# umami-blade.net
KiCad netlist of a schematic drawn in EAGLE
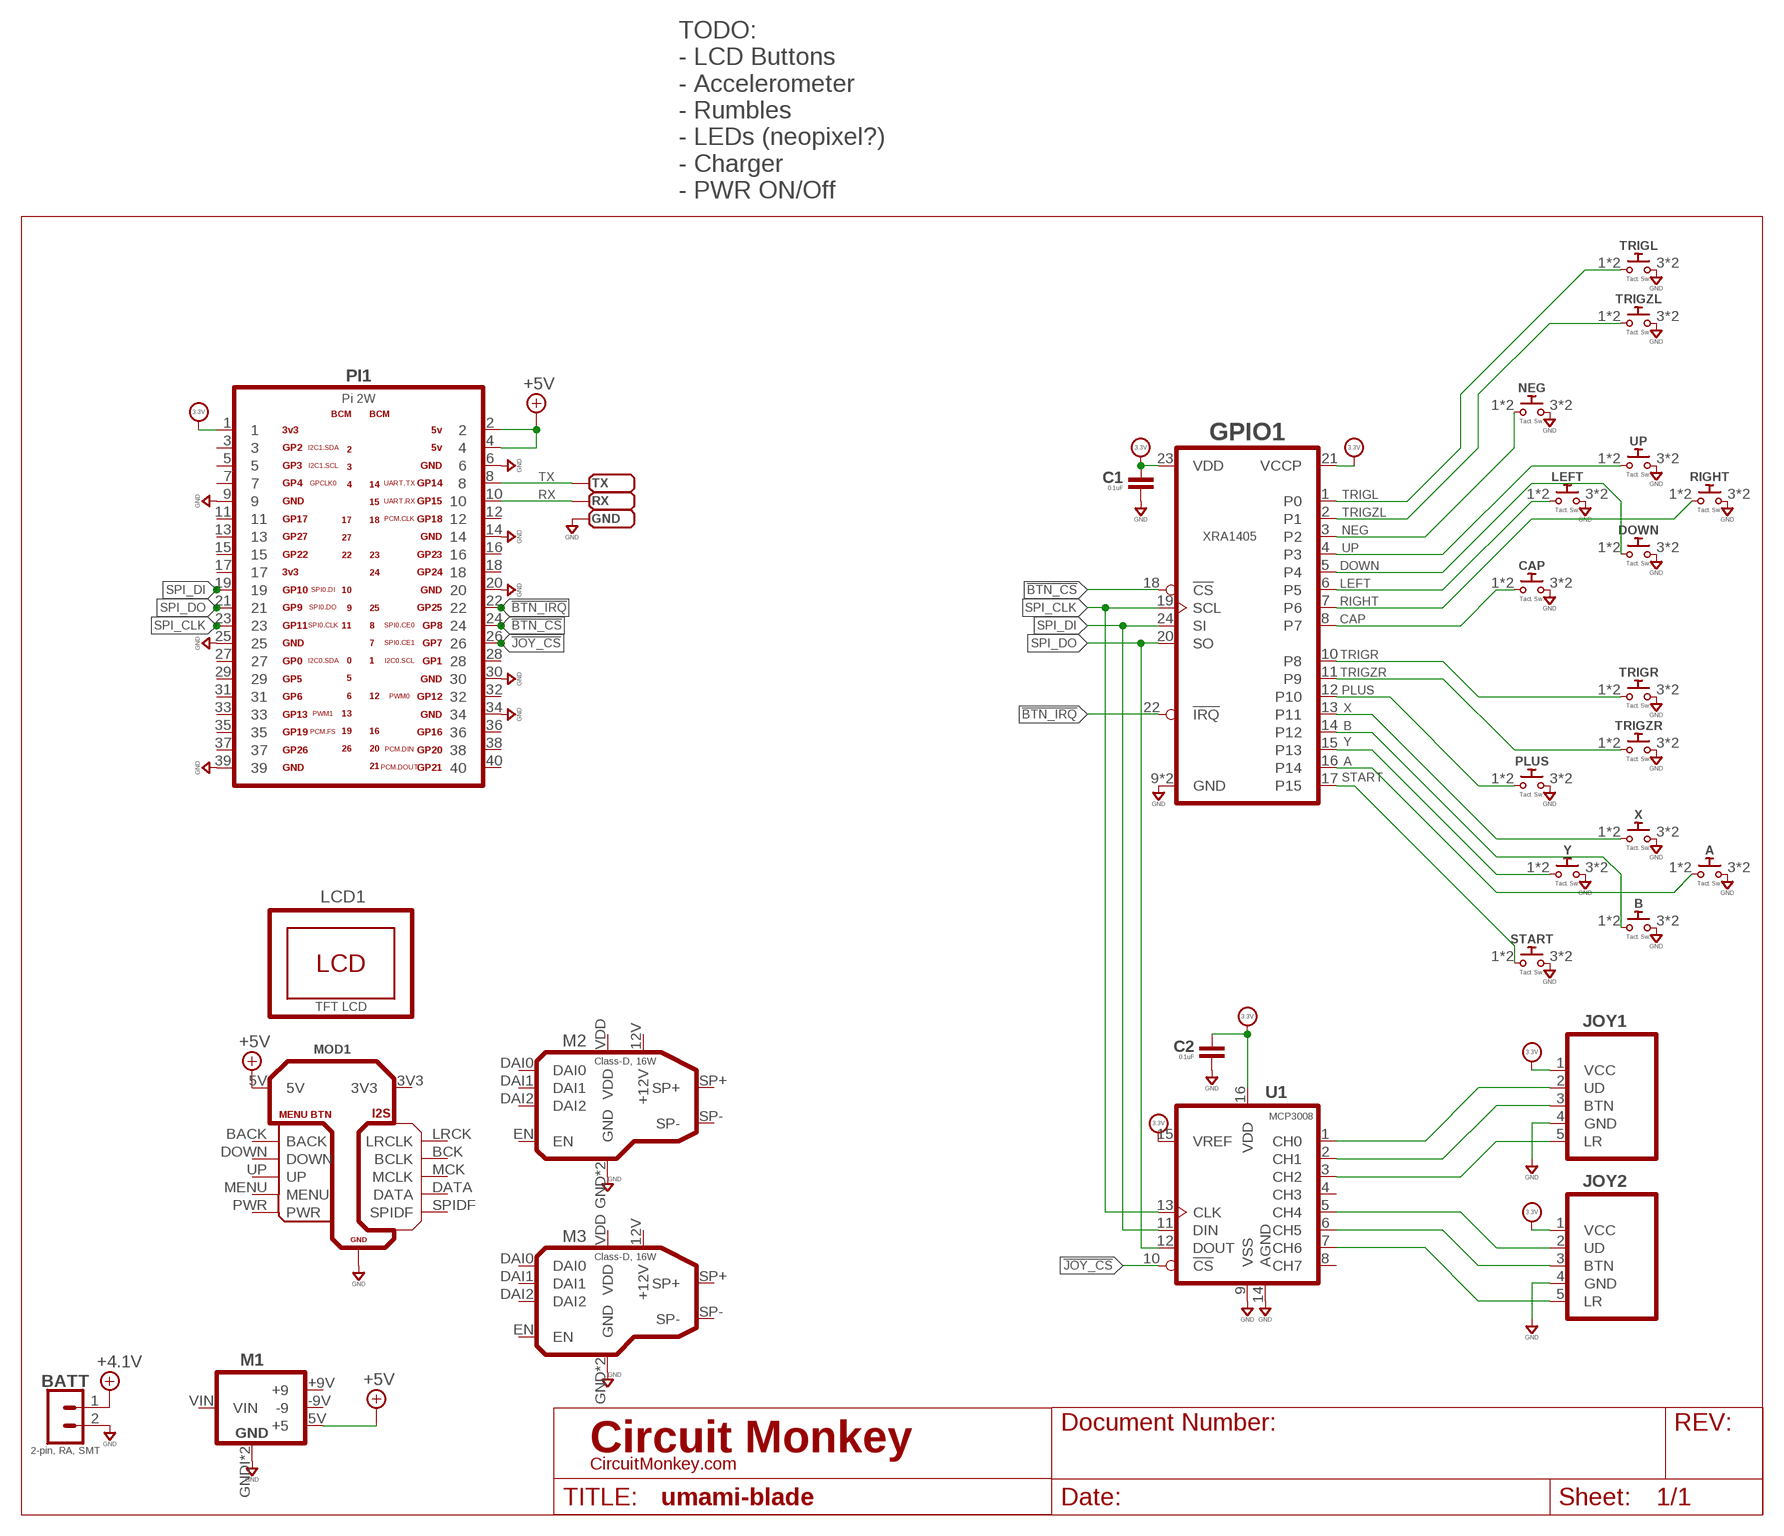
[diagram p0: schematic, sheet 1]

(export (version "E")
  (design (tool "Eeschema 10.0.6"))
  (components
    (comp (ref "A")
      (value "Tact. Sw.")
      (footprint "eagle-import:B3FS")
      (fields (field (name "MFR") "Omron") (field (name "MPN") "B3FS-10*"))
      (libsource (lib "eagle-import") (part "PUSHBTN-MOMB3FS"))
    )
    (comp (ref "B")
      (value "Tact. Sw.")
      (footprint "eagle-import:B3FS")
      (fields (field (name "MFR") "Omron") (field (name "MPN") "B3FS-10*"))
      (libsource (lib "eagle-import") (part "PUSHBTN-MOMB3FS"))
    )
    (comp (ref "BATT")
      (value "2-pin, RA, SMT")
      (footprint "eagle-import:S2B-PH-SM4-")
      (fields (field (name "MFR") "JST") (field (name "MPN") "S2B-PH-SM4"))
      (libsource (lib "eagle-import") (part "02PRA-SMT"))
    )
    (comp (ref "C1")
      (value "0.1uF")
      (footprint "eagle-import:0603-CAP")
      (libsource (lib "eagle-import") (part "CAPACITOR0603"))
    )
    (comp (ref "C2")
      (value "0.1uF")
      (footprint "eagle-import:0603-CAP")
      (libsource (lib "eagle-import") (part "CAPACITOR0603"))
    )
    (comp (ref "CAP")
      (value "Tact. Sw.")
      (footprint "eagle-import:B3FS")
      (fields (field (name "MFR") "Omron") (field (name "MPN") "B3FS-10*"))
      (libsource (lib "eagle-import") (part "PUSHBTN-MOMB3FS"))
    )
    (comp (ref "DOWN")
      (value "Tact. Sw.")
      (footprint "eagle-import:B3FS")
      (fields (field (name "MFR") "Omron") (field (name "MPN") "B3FS-10*"))
      (libsource (lib "eagle-import") (part "PUSHBTN-MOMB3FS"))
    )
    (comp (ref "GND")
      (value "PADSMD-050X050")
      (footprint "eagle-import:SMD-050X050")
      (libsource (lib "eagle-import") (part "PADSMD-050X050"))
    )
    (comp (ref "GPIO1")
      (value "XRA1405")
      (footprint "eagle-import:QFN-24")
      (fields (field (name "MFR") "Exar") (field (name "MPN") "XRA1405IL24"))
      (libsource (lib "eagle-import") (part "XRA1405IL24"))
    )
    (comp (ref "JOY1")
      (value "THUMBSTICKNINTENDO-SWITCH")
      (footprint "eagle-import:NINTENDO-JOYCON")
      (libsource (lib "eagle-import") (part "THUMBSTICKNINTENDO-SWITCH"))
    )
    (comp (ref "JOY2")
      (value "THUMBSTICKNINTENDO-SWITCH")
      (footprint "eagle-import:NINTENDO-JOYCON")
      (libsource (lib "eagle-import") (part "THUMBSTICKNINTENDO-SWITCH"))
    )
    (comp (ref "LCD1")
      (value "TFT LCD")
      (footprint "eagle-import:PIMORONI_PIM372")
      (fields (field (name "MPN") "PIM372"))
      (libsource (lib "eagle-import") (part "LCD_MOCKUPPIM372"))
    )
    (comp (ref "LEFT")
      (value "Tact. Sw.")
      (footprint "eagle-import:B3FS")
      (fields (field (name "MFR") "Omron") (field (name "MPN") "B3FS-10*"))
      (libsource (lib "eagle-import") (part "PUSHBTN-MOMB3FS"))
    )
    (comp (ref "M1")
      (value "0128REV-A")
      (footprint "eagle-import:0128A")
      (libsource (lib "eagle-import") (part "0128REV-A"))
    )
    (comp (ref "M2")
      (value "Class-D, 16W")
      (footprint "eagle-import:0123A")
      (fields (field (name "MFR") "Circuit Monkey") (field (name "MPN") "0123A"))
      (libsource (lib "eagle-import") (part "0123REV-A"))
    )
    (comp (ref "M3")
      (value "Class-D, 16W")
      (footprint "eagle-import:0123A")
      (fields (field (name "MFR") "Circuit Monkey") (field (name "MPN") "0123A"))
      (libsource (lib "eagle-import") (part "0123REV-A"))
    )
    (comp (ref "MOD1")
      (value "LCD_CONTROLLERPIMORONI-8IN")
      (footprint "eagle-import:PIMORONI-LCD-CONTROLLER")
      (libsource (lib "eagle-import") (part "LCD_CONTROLLERPIMORONI-8IN"))
    )
    (comp (ref "NEG")
      (value "Tact. Sw.")
      (footprint "eagle-import:B3FS")
      (fields (field (name "MFR") "Omron") (field (name "MPN") "B3FS-10*"))
      (libsource (lib "eagle-import") (part "PUSHBTN-MOMB3FS"))
    )
    (comp (ref "PI1")
      (value "Pi 2W")
      (footprint "eagle-import:PI-ZERO-2W")
      (libsource (lib "eagle-import") (part "RASPBERRY_PI-ZERO-2W"))
    )
    (comp (ref "PLUS")
      (value "Tact. Sw.")
      (footprint "eagle-import:B3FS")
      (fields (field (name "MFR") "Omron") (field (name "MPN") "B3FS-10*"))
      (libsource (lib "eagle-import") (part "PUSHBTN-MOMB3FS"))
    )
    (comp (ref "RIGHT")
      (value "Tact. Sw.")
      (footprint "eagle-import:B3FS")
      (fields (field (name "MFR") "Omron") (field (name "MPN") "B3FS-10*"))
      (libsource (lib "eagle-import") (part "PUSHBTN-MOMB3FS"))
    )
    (comp (ref "RX")
      (value "PADSMD-050X050")
      (footprint "eagle-import:SMD-050X050")
      (libsource (lib "eagle-import") (part "PADSMD-050X050"))
    )
    (comp (ref "START")
      (value "Tact. Sw.")
      (footprint "eagle-import:B3FS")
      (fields (field (name "MFR") "Omron") (field (name "MPN") "B3FS-10*"))
      (libsource (lib "eagle-import") (part "PUSHBTN-MOMB3FS"))
    )
    (comp (ref "TRIGL")
      (value "Tact. Sw.")
      (footprint "eagle-import:B3FS")
      (fields (field (name "MFR") "Omron") (field (name "MPN") "B3FS-10*"))
      (libsource (lib "eagle-import") (part "PUSHBTN-MOMB3FS"))
    )
    (comp (ref "TRIGR")
      (value "Tact. Sw.")
      (footprint "eagle-import:B3FS")
      (fields (field (name "MFR") "Omron") (field (name "MPN") "B3FS-10*"))
      (libsource (lib "eagle-import") (part "PUSHBTN-MOMB3FS"))
    )
    (comp (ref "TRIGZL")
      (value "Tact. Sw.")
      (footprint "eagle-import:B3FS")
      (fields (field (name "MFR") "Omron") (field (name "MPN") "B3FS-10*"))
      (libsource (lib "eagle-import") (part "PUSHBTN-MOMB3FS"))
    )
    (comp (ref "TRIGZR")
      (value "Tact. Sw.")
      (footprint "eagle-import:B3FS")
      (fields (field (name "MFR") "Omron") (field (name "MPN") "B3FS-10*"))
      (libsource (lib "eagle-import") (part "PUSHBTN-MOMB3FS"))
    )
    (comp (ref "TX")
      (value "PADSMD-050X050")
      (footprint "eagle-import:SMD-050X050")
      (libsource (lib "eagle-import") (part "PADSMD-050X050"))
    )
    (comp (ref "U1")
      (value "MCP3008")
      (footprint "eagle-import:SO16")
      (fields (field (name "MFR") "Microchip") (field (name "MPN") "MCP3008-I/SL"))
      (libsource (lib "eagle-import") (part "MCP3008SO16"))
    )
    (comp (ref "UP")
      (value "Tact. Sw.")
      (footprint "eagle-import:B3FS")
      (fields (field (name "MFR") "Omron") (field (name "MPN") "B3FS-10*"))
      (libsource (lib "eagle-import") (part "PUSHBTN-MOMB3FS"))
    )
    (comp (ref "X")
      (value "Tact. Sw.")
      (footprint "eagle-import:B3FS")
      (fields (field (name "MFR") "Omron") (field (name "MPN") "B3FS-10*"))
      (libsource (lib "eagle-import") (part "PUSHBTN-MOMB3FS"))
    )
    (comp (ref "Y")
      (value "Tact. Sw.")
      (footprint "eagle-import:B3FS")
      (fields (field (name "MFR") "Omron") (field (name "MPN") "B3FS-10*"))
      (libsource (lib "eagle-import") (part "PUSHBTN-MOMB3FS"))
    )
  )
  (nets
    (net (code "1") (name "+4.1V") (class "Default")
      (node (ref "BATT") (pin "1") (pinfunction "1_1") (pintype "passive"))
    )
    (net (code "2") (name "+5V") (class "Default")
      (node (ref "M1") (pin "5V") (pinfunction "+5_5V") (pintype "bidirectional"))
      (node (ref "MOD1") (pin "5V") (pinfunction "5V_5V") (pintype "power_in"))
      (node (ref "PI1") (pin "2") (pinfunction "2_2") (pintype "bidirectional"))
      (node (ref "PI1") (pin "4") (pinfunction "4_4") (pintype "bidirectional"))
    )
    (net (code "3") (name "/A") (class "Default")
      (node (ref "A") (pin "1") (pinfunction "1_1") (pintype "passive"))
      (node (ref "A") (pin "2") (pinfunction "1_2") (pintype "passive"))
      (node (ref "GPIO1") (pin "16") (pinfunction "P14_16") (pintype "bidirectional"))
    )
    (net (code "4") (name "/B") (class "Default")
      (node (ref "B") (pin "1") (pinfunction "1_1") (pintype "passive"))
      (node (ref "B") (pin "2") (pinfunction "1_2") (pintype "passive"))
      (node (ref "GPIO1") (pin "14") (pinfunction "P12_14") (pintype "bidirectional"))
    )
    (net (code "5") (name "/CAP") (class "Default")
      (node (ref "CAP") (pin "1") (pinfunction "1_1") (pintype "passive"))
      (node (ref "CAP") (pin "2") (pinfunction "1_2") (pintype "passive"))
      (node (ref "GPIO1") (pin "8") (pinfunction "P7_8") (pintype "bidirectional"))
    )
    (net (code "6") (name "/DOWN") (class "Default")
      (node (ref "DOWN") (pin "1") (pinfunction "1_1") (pintype "passive"))
      (node (ref "DOWN") (pin "2") (pinfunction "1_2") (pintype "passive"))
      (node (ref "GPIO1") (pin "5") (pinfunction "P4_5") (pintype "bidirectional"))
    )
    (net (code "7") (name "/LEFT") (class "Default")
      (node (ref "GPIO1") (pin "6") (pinfunction "P5_6") (pintype "bidirectional"))
      (node (ref "LEFT") (pin "1") (pinfunction "1_1") (pintype "passive"))
      (node (ref "LEFT") (pin "2") (pinfunction "1_2") (pintype "passive"))
    )
    (net (code "8") (name "/NEG") (class "Default")
      (node (ref "GPIO1") (pin "3") (pinfunction "P2_3") (pintype "bidirectional"))
      (node (ref "NEG") (pin "1") (pinfunction "1_1") (pintype "passive"))
      (node (ref "NEG") (pin "2") (pinfunction "1_2") (pintype "passive"))
    )
    (net (code "9") (name "/PLUS") (class "Default")
      (node (ref "GPIO1") (pin "12") (pinfunction "P10_12") (pintype "bidirectional"))
      (node (ref "PLUS") (pin "1") (pinfunction "1_1") (pintype "passive"))
      (node (ref "PLUS") (pin "2") (pinfunction "1_2") (pintype "passive"))
    )
    (net (code "10") (name "/RIGHT") (class "Default")
      (node (ref "GPIO1") (pin "7") (pinfunction "P6_7") (pintype "bidirectional"))
      (node (ref "RIGHT") (pin "1") (pinfunction "1_1") (pintype "passive"))
      (node (ref "RIGHT") (pin "2") (pinfunction "1_2") (pintype "passive"))
    )
    (net (code "11") (name "/RX") (class "Default")
      (node (ref "PI1") (pin "10") (pinfunction "10_10") (pintype "bidirectional"))
      (node (ref "RX") (pin "1") (pinfunction "PAD_1") (pintype "bidirectional"))
    )
    (net (code "12") (name "/START") (class "Default")
      (node (ref "GPIO1") (pin "17") (pinfunction "P15_17") (pintype "bidirectional"))
      (node (ref "START") (pin "1") (pinfunction "1_1") (pintype "passive"))
      (node (ref "START") (pin "2") (pinfunction "1_2") (pintype "passive"))
    )
    (net (code "13") (name "/TRIGL") (class "Default")
      (node (ref "GPIO1") (pin "1") (pinfunction "P0_1") (pintype "bidirectional"))
      (node (ref "TRIGL") (pin "1") (pinfunction "1_1") (pintype "passive"))
      (node (ref "TRIGL") (pin "2") (pinfunction "1_2") (pintype "passive"))
    )
    (net (code "14") (name "/TRIGR") (class "Default")
      (node (ref "GPIO1") (pin "10") (pinfunction "P8_10") (pintype "bidirectional"))
      (node (ref "TRIGR") (pin "1") (pinfunction "1_1") (pintype "passive"))
      (node (ref "TRIGR") (pin "2") (pinfunction "1_2") (pintype "passive"))
    )
    (net (code "15") (name "/TRIGZL") (class "Default")
      (node (ref "GPIO1") (pin "2") (pinfunction "P1_2") (pintype "bidirectional"))
      (node (ref "TRIGZL") (pin "1") (pinfunction "1_1") (pintype "passive"))
      (node (ref "TRIGZL") (pin "2") (pinfunction "1_2") (pintype "passive"))
    )
    (net (code "16") (name "/TRIGZR") (class "Default")
      (node (ref "GPIO1") (pin "11") (pinfunction "P9_11") (pintype "bidirectional"))
      (node (ref "TRIGZR") (pin "1") (pinfunction "1_1") (pintype "passive"))
      (node (ref "TRIGZR") (pin "2") (pinfunction "1_2") (pintype "passive"))
    )
    (net (code "17") (name "/TX") (class "Default")
      (node (ref "PI1") (pin "8") (pinfunction "8_8") (pintype "bidirectional"))
      (node (ref "TX") (pin "1") (pinfunction "PAD_1") (pintype "bidirectional"))
    )
    (net (code "18") (name "/UP") (class "Default")
      (node (ref "GPIO1") (pin "4") (pinfunction "P3_4") (pintype "bidirectional"))
      (node (ref "UP") (pin "1") (pinfunction "1_1") (pintype "passive"))
      (node (ref "UP") (pin "2") (pinfunction "1_2") (pintype "passive"))
    )
    (net (code "19") (name "/X") (class "Default")
      (node (ref "GPIO1") (pin "13") (pinfunction "P11_13") (pintype "bidirectional"))
      (node (ref "X") (pin "1") (pinfunction "1_1") (pintype "passive"))
      (node (ref "X") (pin "2") (pinfunction "1_2") (pintype "passive"))
    )
    (net (code "20") (name "/Y") (class "Default")
      (node (ref "GPIO1") (pin "15") (pinfunction "P13_15") (pintype "bidirectional"))
      (node (ref "Y") (pin "1") (pinfunction "1_1") (pintype "passive"))
      (node (ref "Y") (pin "2") (pinfunction "1_2") (pintype "passive"))
    )
    (net (code "21") (name "/~{BTN_CS}") (class "Default")
      (node (ref "GPIO1") (pin "18") (pinfunction "~{CS}_18") (pintype "input"))
      (node (ref "PI1") (pin "24") (pinfunction "24_24") (pintype "bidirectional"))
    )
    (net (code "22") (name "/~{BTN_IRQ}") (class "Default")
      (node (ref "GPIO1") (pin "22") (pinfunction "~{IRQ}_22") (pintype "output"))
      (node (ref "PI1") (pin "22") (pinfunction "22_22") (pintype "bidirectional"))
    )
    (net (code "23") (name "/~{JOY_CS}") (class "Default")
      (node (ref "PI1") (pin "26") (pinfunction "26_26") (pintype "bidirectional"))
      (node (ref "U1") (pin "10") (pinfunction "~{CS}_10") (pintype "input"))
    )
    (net (code "24") (name "3.3V") (class "Default")
      (node (ref "C1") (pin "1") (pinfunction "1_1") (pintype "passive"))
      (node (ref "C2") (pin "1") (pinfunction "1_1") (pintype "passive"))
      (node (ref "GPIO1") (pin "21") (pinfunction "VCCP_21") (pintype "power_in"))
      (node (ref "GPIO1") (pin "23") (pinfunction "VDD_23") (pintype "power_in"))
      (node (ref "JOY1") (pin "1") (pinfunction "VCC_1") (pintype "bidirectional"))
      (node (ref "JOY2") (pin "1") (pinfunction "VCC_1") (pintype "bidirectional"))
      (node (ref "PI1") (pin "1") (pinfunction "1_1") (pintype "bidirectional"))
      (node (ref "U1") (pin "15") (pinfunction "VREF_15") (pintype "input"))
      (node (ref "U1") (pin "16") (pinfunction "VDD_16") (pintype "bidirectional"))
    )
    (net (code "25") (name "GND") (class "Default")
      (node (ref "A") (pin "3") (pinfunction "2_3") (pintype "passive"))
      (node (ref "A") (pin "4") (pinfunction "2_4") (pintype "passive"))
      (node (ref "B") (pin "3") (pinfunction "2_3") (pintype "passive"))
      (node (ref "B") (pin "4") (pinfunction "2_4") (pintype "passive"))
      (node (ref "BATT") (pin "2") (pinfunction "2_2") (pintype "passive"))
      (node (ref "C1") (pin "2") (pinfunction "2_2") (pintype "passive"))
      (node (ref "C2") (pin "2") (pinfunction "2_2") (pintype "passive"))
      (node (ref "CAP") (pin "3") (pinfunction "2_3") (pintype "passive"))
      (node (ref "CAP") (pin "4") (pinfunction "2_4") (pintype "passive"))
      (node (ref "DOWN") (pin "3") (pinfunction "2_3") (pintype "passive"))
      (node (ref "DOWN") (pin "4") (pinfunction "2_4") (pintype "passive"))
      (node (ref "GND") (pin "1") (pinfunction "PAD_1") (pintype "bidirectional"))
      (node (ref "GPIO1") (pin "9") (pinfunction "GND_9") (pintype "power_in"))
      (node (ref "GPIO1") (pin "PAD") (pinfunction "GND_PAD") (pintype "power_in"))
      (node (ref "JOY1") (pin "4") (pinfunction "GND_4") (pintype "bidirectional"))
      (node (ref "JOY2") (pin "4") (pinfunction "GND_4") (pintype "bidirectional"))
      (node (ref "LEFT") (pin "3") (pinfunction "2_3") (pintype "passive"))
      (node (ref "LEFT") (pin "4") (pinfunction "2_4") (pintype "passive"))
      (node (ref "M1") (pin "GNDI") (pinfunction "GND_GNDI") (pintype "bidirectional"))
      (node (ref "M1") (pin "GNDO") (pinfunction "GND_GNDO") (pintype "bidirectional"))
      (node (ref "M2") (pin "GND") (pinfunction "GND_GND") (pintype "bidirectional"))
      (node (ref "M2") (pin "GND2") (pinfunction "GND_GND2") (pintype "bidirectional"))
      (node (ref "M3") (pin "GND") (pinfunction "GND_GND") (pintype "bidirectional"))
      (node (ref "M3") (pin "GND2") (pinfunction "GND_GND2") (pintype "bidirectional"))
      (node (ref "MOD1") (pin "GND@I2S") (pinfunction "GND_GND@I2S") (pintype "bidirectional"))
      (node (ref "MOD1") (pin "GND@MENU") (pinfunction "GND_GND@MENU") (pintype "bidirectional"))
      (node (ref "NEG") (pin "3") (pinfunction "2_3") (pintype "passive"))
      (node (ref "NEG") (pin "4") (pinfunction "2_4") (pintype "passive"))
      (node (ref "PI1") (pin "14") (pinfunction "14_14") (pintype "bidirectional"))
      (node (ref "PI1") (pin "20") (pinfunction "20_20") (pintype "bidirectional"))
      (node (ref "PI1") (pin "25") (pinfunction "25_25") (pintype "bidirectional"))
      (node (ref "PI1") (pin "30") (pinfunction "30_30") (pintype "bidirectional"))
      (node (ref "PI1") (pin "34") (pinfunction "34_34") (pintype "bidirectional"))
      (node (ref "PI1") (pin "39") (pinfunction "39_39") (pintype "bidirectional"))
      (node (ref "PI1") (pin "6") (pinfunction "6_6") (pintype "bidirectional"))
      (node (ref "PI1") (pin "9") (pinfunction "9_9") (pintype "bidirectional"))
      (node (ref "PLUS") (pin "3") (pinfunction "2_3") (pintype "passive"))
      (node (ref "PLUS") (pin "4") (pinfunction "2_4") (pintype "passive"))
      (node (ref "RIGHT") (pin "3") (pinfunction "2_3") (pintype "passive"))
      (node (ref "RIGHT") (pin "4") (pinfunction "2_4") (pintype "passive"))
      (node (ref "START") (pin "3") (pinfunction "2_3") (pintype "passive"))
      (node (ref "START") (pin "4") (pinfunction "2_4") (pintype "passive"))
      (node (ref "TRIGL") (pin "3") (pinfunction "2_3") (pintype "passive"))
      (node (ref "TRIGL") (pin "4") (pinfunction "2_4") (pintype "passive"))
      (node (ref "TRIGR") (pin "3") (pinfunction "2_3") (pintype "passive"))
      (node (ref "TRIGR") (pin "4") (pinfunction "2_4") (pintype "passive"))
      (node (ref "TRIGZL") (pin "3") (pinfunction "2_3") (pintype "passive"))
      (node (ref "TRIGZL") (pin "4") (pinfunction "2_4") (pintype "passive"))
      (node (ref "TRIGZR") (pin "3") (pinfunction "2_3") (pintype "passive"))
      (node (ref "TRIGZR") (pin "4") (pinfunction "2_4") (pintype "passive"))
      (node (ref "U1") (pin "14") (pinfunction "AGND_14") (pintype "bidirectional"))
      (node (ref "U1") (pin "9") (pinfunction "VSS_9") (pintype "bidirectional"))
      (node (ref "UP") (pin "3") (pinfunction "2_3") (pintype "passive"))
      (node (ref "UP") (pin "4") (pinfunction "2_4") (pintype "passive"))
      (node (ref "X") (pin "3") (pinfunction "2_3") (pintype "passive"))
      (node (ref "X") (pin "4") (pinfunction "2_4") (pintype "passive"))
      (node (ref "Y") (pin "3") (pinfunction "2_3") (pintype "passive"))
      (node (ref "Y") (pin "4") (pinfunction "2_4") (pintype "passive"))
    )
    (net (code "26") (name "Net-(JOY1-BTN)") (class "Default")
      (node (ref "JOY1") (pin "3") (pinfunction "BTN_3") (pintype "bidirectional"))
      (node (ref "U1") (pin "2") (pinfunction "CH1_2") (pintype "input"))
    )
    (net (code "27") (name "Net-(JOY1-LR)") (class "Default")
      (node (ref "JOY1") (pin "5") (pinfunction "LR_5") (pintype "bidirectional"))
      (node (ref "U1") (pin "3") (pinfunction "CH2_3") (pintype "input"))
    )
    (net (code "28") (name "Net-(JOY1-UD)") (class "Default")
      (node (ref "JOY1") (pin "2") (pinfunction "UD_2") (pintype "bidirectional"))
      (node (ref "U1") (pin "1") (pinfunction "CH0_1") (pintype "input"))
    )
    (net (code "29") (name "Net-(JOY2-BTN)") (class "Default")
      (node (ref "JOY2") (pin "3") (pinfunction "BTN_3") (pintype "bidirectional"))
      (node (ref "U1") (pin "6") (pinfunction "CH5_6") (pintype "input"))
    )
    (net (code "30") (name "Net-(JOY2-LR)") (class "Default")
      (node (ref "JOY2") (pin "5") (pinfunction "LR_5") (pintype "bidirectional"))
      (node (ref "U1") (pin "7") (pinfunction "CH6_7") (pintype "input"))
    )
    (net (code "31") (name "Net-(JOY2-UD)") (class "Default")
      (node (ref "JOY2") (pin "2") (pinfunction "UD_2") (pintype "bidirectional"))
      (node (ref "U1") (pin "5") (pinfunction "CH4_5") (pintype "input"))
    )
    (net (code "32") (name "SPI_CLK") (class "Default")
      (node (ref "GPIO1") (pin "19") (pinfunction "SCL_19") (pintype "input"))
      (node (ref "PI1") (pin "23") (pinfunction "23_23") (pintype "bidirectional"))
      (node (ref "U1") (pin "13") (pinfunction "CLK_13") (pintype "bidirectional"))
    )
    (net (code "33") (name "SPI_DI") (class "Default")
      (node (ref "GPIO1") (pin "24") (pinfunction "SI_24") (pintype "input"))
      (node (ref "PI1") (pin "19") (pinfunction "19_19") (pintype "bidirectional"))
      (node (ref "U1") (pin "11") (pinfunction "DIN_11") (pintype "input"))
    )
    (net (code "34") (name "SPI_DO") (class "Default")
      (node (ref "GPIO1") (pin "20") (pinfunction "SO_20") (pintype "output"))
      (node (ref "PI1") (pin "21") (pinfunction "21_21") (pintype "bidirectional"))
      (node (ref "U1") (pin "12") (pinfunction "DOUT_12") (pintype "output"))
    )
    (net (code "35") (name "unconnected-(M1-+9-Pad+9V)") (class "Default")
      (node (ref "M1") (pin "+9V") (pinfunction "+9_+9V") (pintype "bidirectional"))
    )
    (net (code "36") (name "unconnected-(M1--9-Pad-9V)") (class "Default")
      (node (ref "M1") (pin "-9V") (pinfunction "-9_-9V") (pintype "bidirectional"))
    )
    (net (code "37") (name "unconnected-(M1-PadVIN)") (class "Default")
      (node (ref "M1") (pin "VIN") (pinfunction "VIN_VIN") (pintype "bidirectional"))
    )
    (net (code "38") (name "unconnected-(M2-+12V-Pad12V)") (class "Default")
      (node (ref "M2") (pin "12V") (pinfunction "+12V_12V") (pintype "bidirectional"))
    )
    (net (code "39") (name "unconnected-(M2-PadDAI0)") (class "Default")
      (node (ref "M2") (pin "DAI0") (pinfunction "DAI0_DAI0") (pintype "bidirectional"))
    )
    (net (code "40") (name "unconnected-(M2-PadDAI1)") (class "Default")
      (node (ref "M2") (pin "DAI1") (pinfunction "DAI1_DAI1") (pintype "bidirectional"))
    )
    (net (code "41") (name "unconnected-(M2-PadDAI2)") (class "Default")
      (node (ref "M2") (pin "DAI2") (pinfunction "DAI2_DAI2") (pintype "bidirectional"))
    )
    (net (code "42") (name "unconnected-(M2-PadEN)") (class "Default")
      (node (ref "M2") (pin "EN") (pinfunction "EN_EN") (pintype "bidirectional"))
    )
    (net (code "43") (name "unconnected-(M2-PadSP+)") (class "Default")
      (node (ref "M2") (pin "SP+") (pinfunction "SP+_SP+") (pintype "bidirectional"))
    )
    (net (code "44") (name "unconnected-(M2-PadSP-)") (class "Default")
      (node (ref "M2") (pin "SP-") (pinfunction "SP-_SP-") (pintype "bidirectional"))
    )
    (net (code "45") (name "unconnected-(M2-PadVDD)") (class "Default")
      (node (ref "M2") (pin "VDD") (pinfunction "VDD_VDD") (pintype "bidirectional"))
    )
    (net (code "46") (name "unconnected-(M3-+12V-Pad12V)") (class "Default")
      (node (ref "M3") (pin "12V") (pinfunction "+12V_12V") (pintype "bidirectional"))
    )
    (net (code "47") (name "unconnected-(M3-PadDAI0)") (class "Default")
      (node (ref "M3") (pin "DAI0") (pinfunction "DAI0_DAI0") (pintype "bidirectional"))
    )
    (net (code "48") (name "unconnected-(M3-PadDAI1)") (class "Default")
      (node (ref "M3") (pin "DAI1") (pinfunction "DAI1_DAI1") (pintype "bidirectional"))
    )
    (net (code "49") (name "unconnected-(M3-PadDAI2)") (class "Default")
      (node (ref "M3") (pin "DAI2") (pinfunction "DAI2_DAI2") (pintype "bidirectional"))
    )
    (net (code "50") (name "unconnected-(M3-PadEN)") (class "Default")
      (node (ref "M3") (pin "EN") (pinfunction "EN_EN") (pintype "bidirectional"))
    )
    (net (code "51") (name "unconnected-(M3-PadSP+)") (class "Default")
      (node (ref "M3") (pin "SP+") (pinfunction "SP+_SP+") (pintype "bidirectional"))
    )
    (net (code "52") (name "unconnected-(M3-PadSP-)") (class "Default")
      (node (ref "M3") (pin "SP-") (pinfunction "SP-_SP-") (pintype "bidirectional"))
    )
    (net (code "53") (name "unconnected-(M3-PadVDD)") (class "Default")
      (node (ref "M3") (pin "VDD") (pinfunction "VDD_VDD") (pintype "bidirectional"))
    )
    (net (code "54") (name "unconnected-(MOD1-BCLK-PadBCK)") (class "Default")
      (node (ref "MOD1") (pin "BCK") (pinfunction "BCLK_BCK") (pintype "output"))
    )
    (net (code "55") (name "unconnected-(MOD1-LRCLK-PadLRCK)") (class "Default")
      (node (ref "MOD1") (pin "LRCK") (pinfunction "LRCLK_LRCK") (pintype "output"))
    )
    (net (code "56") (name "unconnected-(MOD1-MCLK-PadMCK)") (class "Default")
      (node (ref "MOD1") (pin "MCK") (pinfunction "MCLK_MCK") (pintype "output"))
    )
    (net (code "57") (name "unconnected-(MOD1-Pad3V3)") (class "Default")
      (node (ref "MOD1") (pin "3V3") (pinfunction "3V3_3V3") (pintype "output"))
    )
    (net (code "58") (name "unconnected-(MOD1-PadBACK)") (class "Default")
      (node (ref "MOD1") (pin "BACK") (pinfunction "BACK_BACK") (pintype "input"))
    )
    (net (code "59") (name "unconnected-(MOD1-PadDATA)") (class "Default")
      (node (ref "MOD1") (pin "DATA") (pinfunction "DATA_DATA") (pintype "output"))
    )
    (net (code "60") (name "unconnected-(MOD1-PadDOWN)") (class "Default")
      (node (ref "MOD1") (pin "DOWN") (pinfunction "DOWN_DOWN") (pintype "input"))
    )
    (net (code "61") (name "unconnected-(MOD1-PadMENU)") (class "Default")
      (node (ref "MOD1") (pin "MENU") (pinfunction "MENU_MENU") (pintype "input"))
    )
    (net (code "62") (name "unconnected-(MOD1-PadPWR)") (class "Default")
      (node (ref "MOD1") (pin "PWR") (pinfunction "PWR_PWR") (pintype "input"))
    )
    (net (code "63") (name "unconnected-(MOD1-PadSPIDF)") (class "Default")
      (node (ref "MOD1") (pin "SPIDF") (pinfunction "SPIDF_SPIDF") (pintype "output"))
    )
    (net (code "64") (name "unconnected-(MOD1-PadUP)") (class "Default")
      (node (ref "MOD1") (pin "UP") (pinfunction "UP_UP") (pintype "input"))
    )
    (net (code "65") (name "unconnected-(PI1-Pad3)") (class "Default")
      (node (ref "PI1") (pin "3") (pinfunction "3_3") (pintype "bidirectional"))
    )
    (net (code "66") (name "unconnected-(PI1-Pad5)") (class "Default")
      (node (ref "PI1") (pin "5") (pinfunction "5_5") (pintype "bidirectional"))
    )
    (net (code "67") (name "unconnected-(PI1-Pad7)") (class "Default")
      (node (ref "PI1") (pin "7") (pinfunction "7_7") (pintype "bidirectional"))
    )
    (net (code "68") (name "unconnected-(PI1-Pad11)") (class "Default")
      (node (ref "PI1") (pin "11") (pinfunction "11_11") (pintype "bidirectional"))
    )
    (net (code "69") (name "unconnected-(PI1-Pad12)") (class "Default")
      (node (ref "PI1") (pin "12") (pinfunction "12_12") (pintype "bidirectional"))
    )
    (net (code "70") (name "unconnected-(PI1-Pad13)") (class "Default")
      (node (ref "PI1") (pin "13") (pinfunction "13_13") (pintype "bidirectional"))
    )
    (net (code "71") (name "unconnected-(PI1-Pad15)") (class "Default")
      (node (ref "PI1") (pin "15") (pinfunction "15_15") (pintype "bidirectional"))
    )
    (net (code "72") (name "unconnected-(PI1-Pad16)") (class "Default")
      (node (ref "PI1") (pin "16") (pinfunction "16_16") (pintype "bidirectional"))
    )
    (net (code "73") (name "unconnected-(PI1-Pad17)") (class "Default")
      (node (ref "PI1") (pin "17") (pinfunction "17_17") (pintype "bidirectional"))
    )
    (net (code "74") (name "unconnected-(PI1-Pad18)") (class "Default")
      (node (ref "PI1") (pin "18") (pinfunction "18_18") (pintype "bidirectional"))
    )
    (net (code "75") (name "unconnected-(PI1-Pad27)") (class "Default")
      (node (ref "PI1") (pin "27") (pinfunction "27_27") (pintype "bidirectional"))
    )
    (net (code "76") (name "unconnected-(PI1-Pad28)") (class "Default")
      (node (ref "PI1") (pin "28") (pinfunction "28_28") (pintype "bidirectional"))
    )
    (net (code "77") (name "unconnected-(PI1-Pad29)") (class "Default")
      (node (ref "PI1") (pin "29") (pinfunction "29_29") (pintype "bidirectional"))
    )
    (net (code "78") (name "unconnected-(PI1-Pad31)") (class "Default")
      (node (ref "PI1") (pin "31") (pinfunction "31_31") (pintype "bidirectional"))
    )
    (net (code "79") (name "unconnected-(PI1-Pad32)") (class "Default")
      (node (ref "PI1") (pin "32") (pinfunction "32_32") (pintype "bidirectional"))
    )
    (net (code "80") (name "unconnected-(PI1-Pad33)") (class "Default")
      (node (ref "PI1") (pin "33") (pinfunction "33_33") (pintype "bidirectional"))
    )
    (net (code "81") (name "unconnected-(PI1-Pad35)") (class "Default")
      (node (ref "PI1") (pin "35") (pinfunction "35_35") (pintype "bidirectional"))
    )
    (net (code "82") (name "unconnected-(PI1-Pad36)") (class "Default")
      (node (ref "PI1") (pin "36") (pinfunction "36_36") (pintype "bidirectional"))
    )
    (net (code "83") (name "unconnected-(PI1-Pad37)") (class "Default")
      (node (ref "PI1") (pin "37") (pinfunction "37_37") (pintype "bidirectional"))
    )
    (net (code "84") (name "unconnected-(PI1-Pad38)") (class "Default")
      (node (ref "PI1") (pin "38") (pinfunction "38_38") (pintype "bidirectional"))
    )
    (net (code "85") (name "unconnected-(PI1-Pad40)") (class "Default")
      (node (ref "PI1") (pin "40") (pinfunction "40_40") (pintype "bidirectional"))
    )
    (net (code "86") (name "unconnected-(U1-CH3-Pad4)") (class "Default")
      (node (ref "U1") (pin "4") (pinfunction "CH3_4") (pintype "input"))
    )
    (net (code "87") (name "unconnected-(U1-CH7-Pad8)") (class "Default")
      (node (ref "U1") (pin "8") (pinfunction "CH7_8") (pintype "input"))
    )
  )
)
